# Memory.net
KiCad netlist of a schematic drawn in Altium Designer
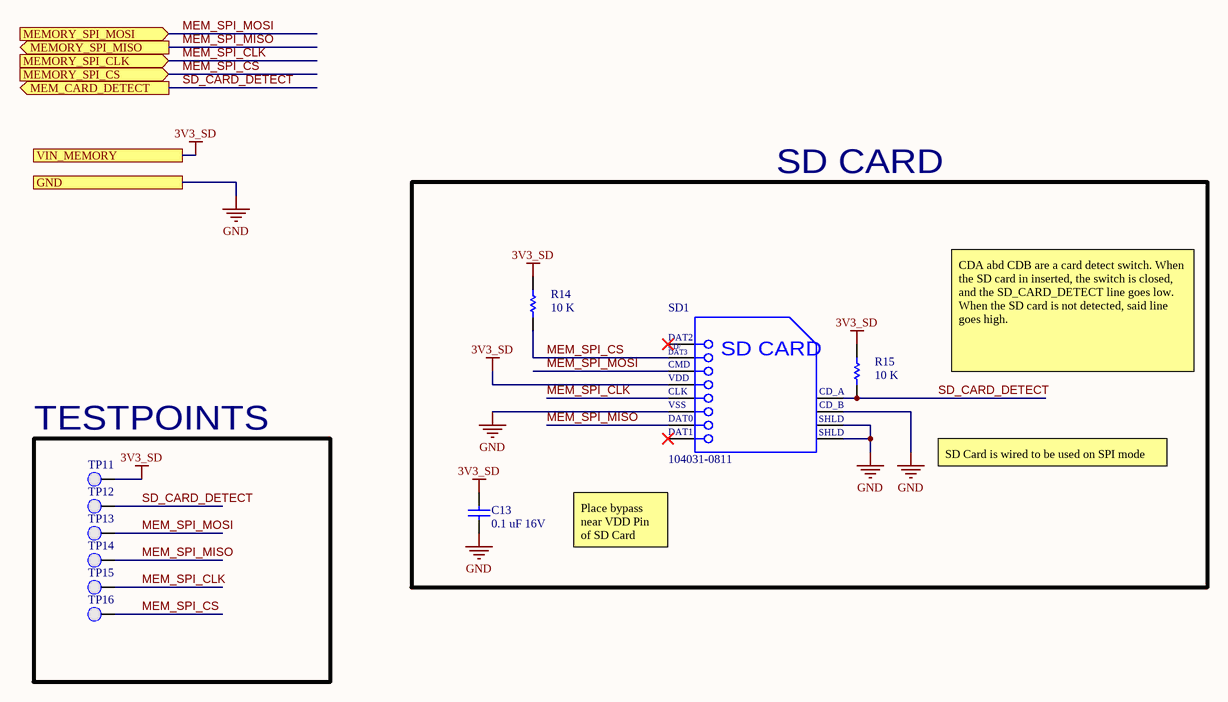
[diagram p0: Memory.SchDoc]

(export (version "E")
  (design (tool "Eeschema 10.0.6"))
  (components
    (comp (ref "C13")
      (value "0.1 uF 16V")
      (footprint "CAPC1608X95X40LL15T15")
      (description "VJ0603Y104KXJCW1BC")
      (fields (field (name "MANUFACTURER") "Vitramon"))
      (libsource (lib "Altium Content Vault") (part "CAP"))
    )
    (comp (ref "R14")
      (value "10 K")
      (footprint "RESC1609X55X30LL15T15")
      (description "Chip Resistor, 10 KOhm, +/- 1%, 0.1 W, -55 to 155 degC, 0603 (1608 Metric), RoHS, Tape and Reel")
      (fields (field (name "TOLERANCE") "1%") (field (name "MANUFACTURER") "Panasonic"))
      (libsource (lib "Altium Content Vault") (part "RES-2"))
    )
    (comp (ref "R15")
      (value "10 K")
      (footprint "RESC1609X55X30LL15T15")
      (description "Chip Resistor, 10 KOhm, +/- 1%, 0.1 W, -55 to 155 degC, 0603 (1608 Metric), RoHS, Tape and Reel")
      (fields (field (name "TOLERANCE") "1%") (field (name "MANUFACTURER") "Panasonic"))
      (libsource (lib "Altium Content Vault") (part "RES-2"))
    )
    (comp (ref "SD1")
      (value "104031-0811")
      (footprint "MOLX-104031-0811_V")
      (description "Micro SD Card, RA, -25 to 85 degC, 8-Pin SMD, RoHS, Tape and Reel")
      (fields (field (name "MANUFACTURER") "Molex"))
      (libsource (lib "Altium Content Vault") (part "CN-SD-8-2SW-2S"))
    )
    (comp (ref "TP11")
      (value "0.1\" Pad")
      (footprint "PCBComponent")
      (libsource (lib "Components - 12.02.20 - 18.05") (part "0.1{dblquote} Pad-A.4"))
    )
    (comp (ref "TP12")
      (value "0.1\" Pad")
      (footprint "PCBComponent")
      (libsource (lib "Components - 12.02.20 - 18.05") (part "0.1{dblquote} Pad-A.4"))
    )
    (comp (ref "TP13")
      (value "0.1\" Pad")
      (footprint "PCBComponent")
      (libsource (lib "Components - 12.02.20 - 18.05") (part "0.1{dblquote} Pad-A.4"))
    )
    (comp (ref "TP14")
      (value "0.1\" Pad")
      (footprint "PCBComponent")
      (libsource (lib "Components - 12.02.20 - 18.05") (part "0.1{dblquote} Pad-A.4"))
    )
    (comp (ref "TP15")
      (value "0.1\" Pad")
      (footprint "PCBComponent")
      (libsource (lib "Components - 12.02.20 - 18.05") (part "0.1{dblquote} Pad-A.4"))
    )
    (comp (ref "TP16")
      (value "0.1\" Pad")
      (footprint "PCBComponent")
      (libsource (lib "Components - 12.02.20 - 18.05") (part "0.1{dblquote} Pad-A.4"))
    )
  )
  (nets
    (net (code "1") (name "/MEM_SPI_CLK") (class "Default")
      (node (ref "SD1") (pin "5") (pinfunction "CLK_5") (pintype "passive"))
      (node (ref "TP15") (pin "1") (pinfunction "PAD_1") (pintype "passive"))
    )
    (net (code "2") (name "/MEM_SPI_CS") (class "Default")
      (node (ref "R14") (pin "1") (pinfunction "1_1") (pintype "passive"))
      (node (ref "SD1") (pin "2") (pinfunction "CMD_2") (pintype "passive"))
      (node (ref "TP16") (pin "1") (pinfunction "PAD_1") (pintype "passive"))
    )
    (net (code "3") (name "/MEM_SPI_MISO") (class "Default")
      (node (ref "SD1") (pin "7") (pinfunction "DAT0_7") (pintype "passive"))
      (node (ref "TP14") (pin "1") (pinfunction "PAD_1") (pintype "passive"))
    )
    (net (code "4") (name "/MEM_SPI_MOSI") (class "Default")
      (node (ref "SD1") (pin "3") (pinfunction "VSS1_3") (pintype "passive"))
      (node (ref "TP13") (pin "1") (pinfunction "PAD_1") (pintype "passive"))
    )
    (net (code "5") (name "/SD_CARD_DETECT") (class "Default")
      (node (ref "R15") (pin "1") (pinfunction "1_1") (pintype "passive"))
      (node (ref "SD1") (pin "9") (pinfunction "CD_A_9") (pintype "passive"))
      (node (ref "TP12") (pin "1") (pinfunction "PAD_1") (pintype "passive"))
    )
    (net (code "6") (name "3V3_SD") (class "Default")
      (node (ref "C13") (pin "2") (pinfunction "2_2") (pintype "passive"))
      (node (ref "R14") (pin "2") (pinfunction "2_2") (pintype "passive"))
      (node (ref "R15") (pin "2") (pinfunction "2_2") (pintype "passive"))
      (node (ref "SD1") (pin "4") (pinfunction "VDD_4") (pintype "passive"))
      (node (ref "TP11") (pin "1") (pinfunction "PAD_1") (pintype "passive"))
    )
    (net (code "7") (name "GND") (class "Default")
      (node (ref "C13") (pin "1") (pinfunction "1_1") (pintype "passive"))
      (node (ref "SD1") (pin "10") (pinfunction "CD_B_10") (pintype "passive"))
      (node (ref "SD1") (pin "11") (pinfunction "SHLD1_11") (pintype "passive"))
      (node (ref "SD1") (pin "12") (pinfunction "SHLD2_12") (pintype "passive"))
      (node (ref "SD1") (pin "6") (pinfunction "VSS2_6") (pintype "passive"))
    )
    (net (code "8") (name "unconnected-(SD1-CD{slash}DAT3-Pad1)") (class "Default")
      (node (ref "SD1") (pin "1") (pinfunction "CD/DAT3_1") (pintype "passive+no_connect"))
    )
    (net (code "9") (name "unconnected-(SD1-DAT1-Pad8)") (class "Default")
      (node (ref "SD1") (pin "8") (pinfunction "DAT1_8") (pintype "passive+no_connect"))
    )
  )
)
